# MotioGlove.net
KiCad netlist of a schematic drawn in EAGLE
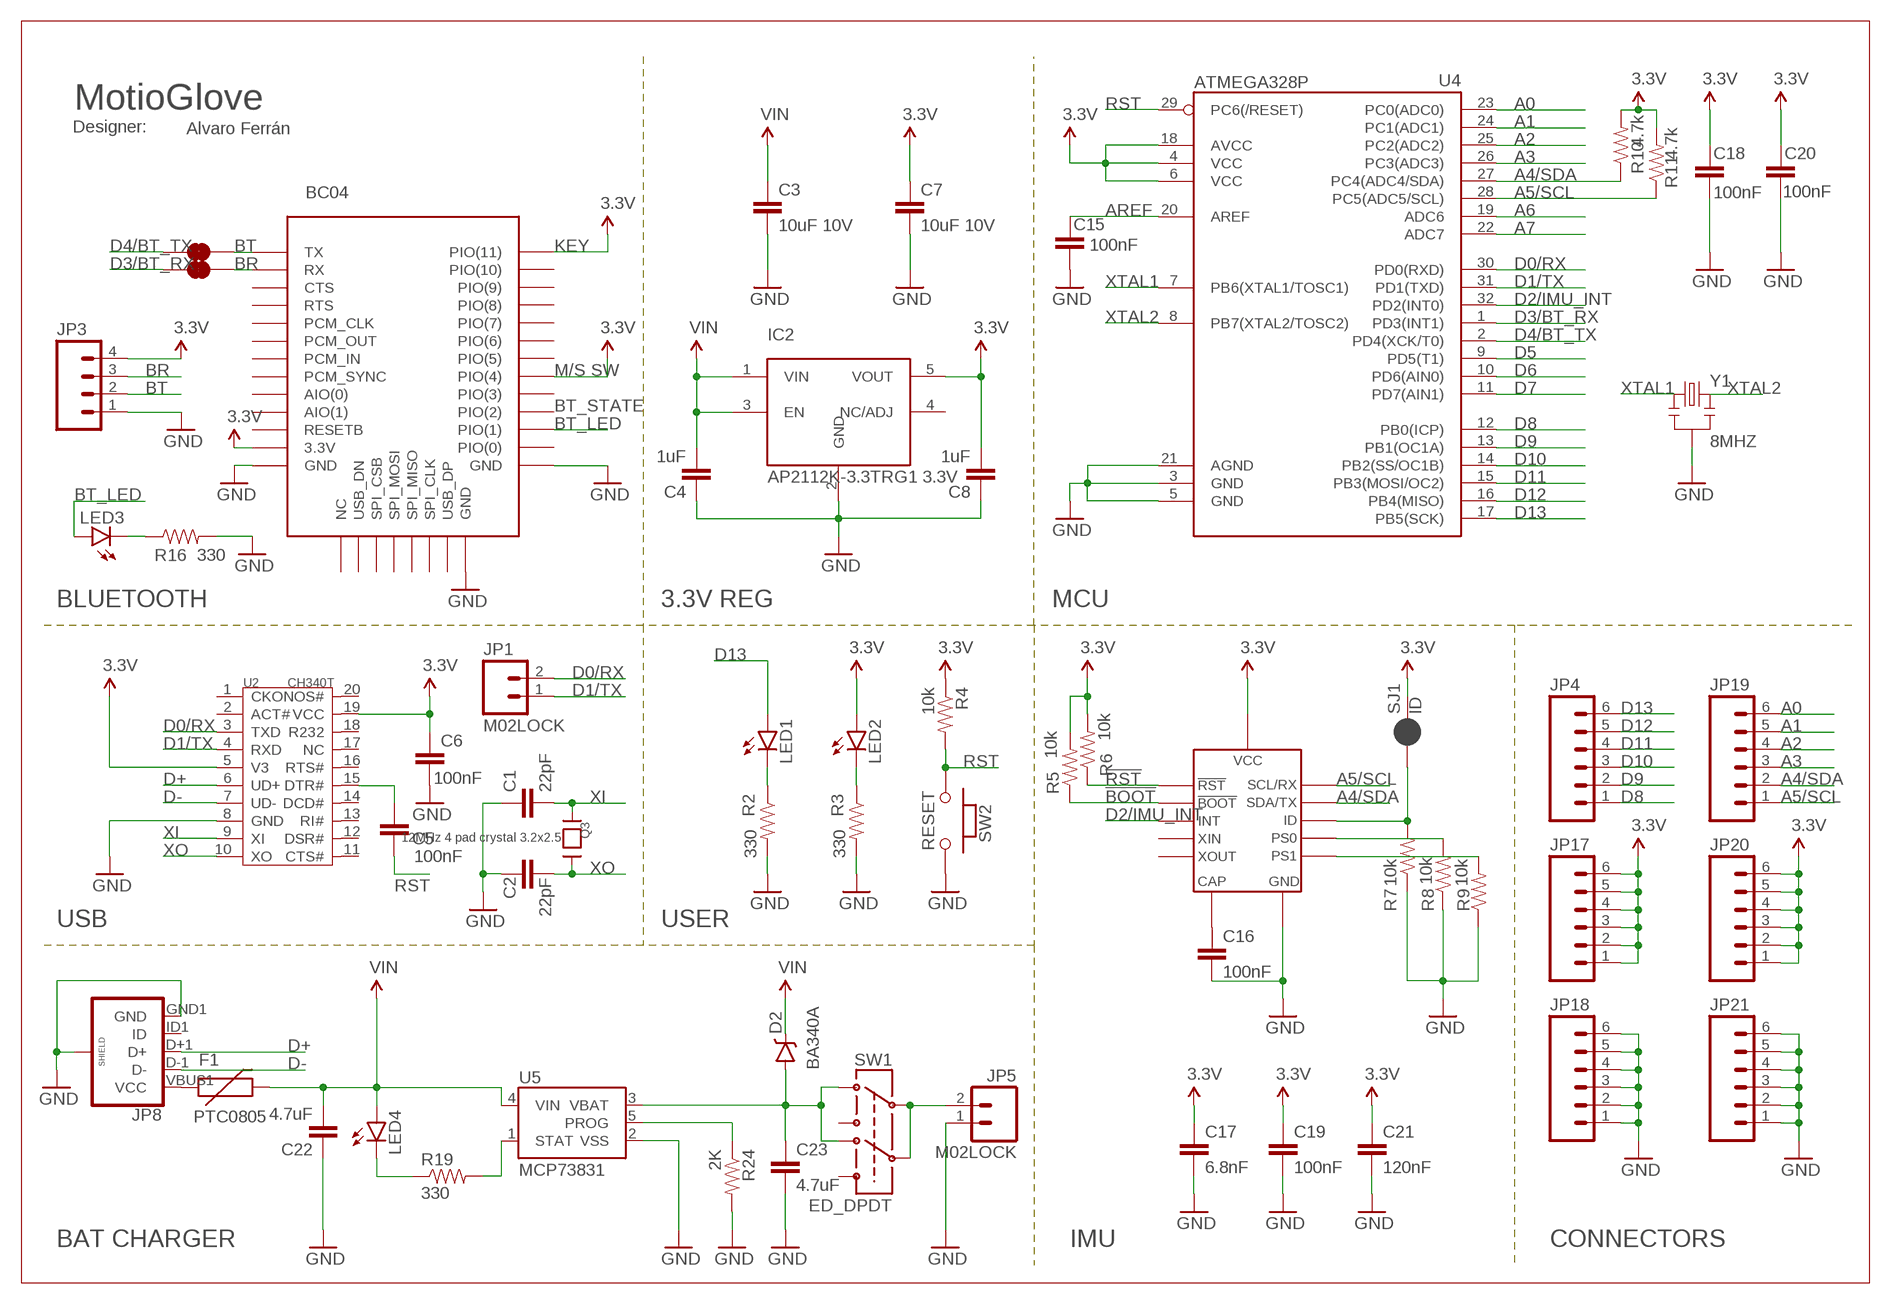
[diagram p0: schematic, sheet 1]

(export (version "E")
  (design (tool "Eeschema 10.0.6"))
  (components
    (comp (ref "C1")
      (value "22pF")
      (footprint "eagle-import:0402-CAP")
      (libsource (lib "eagle-import") (part "CAP0402-CAP"))
    )
    (comp (ref "C2")
      (value "22pF")
      (footprint "eagle-import:0402-CAP")
      (libsource (lib "eagle-import") (part "CAP0402-CAP"))
    )
    (comp (ref "C3")
      (value "10uF 10V")
      (footprint "eagle-import:0603-CAP")
      (libsource (lib "eagle-import") (part "CAP0603-CAP"))
    )
    (comp (ref "C4")
      (value "1uF")
      (footprint "eagle-import:0603-CAP")
      (libsource (lib "eagle-import") (part "CAP0603-CAP"))
    )
    (comp (ref "C5")
      (value "100nF")
      (footprint "eagle-import:0402-CAP")
      (libsource (lib "eagle-import") (part "CAP0402-CAP"))
    )
    (comp (ref "C6")
      (value "100nF")
      (footprint "eagle-import:0402-CAP")
      (libsource (lib "eagle-import") (part "CAP0402-CAP"))
    )
    (comp (ref "C7")
      (value "10uF 10V")
      (footprint "eagle-import:0603-CAP")
      (libsource (lib "eagle-import") (part "CAP0603-CAP"))
    )
    (comp (ref "C8")
      (value "1uF")
      (footprint "eagle-import:0603-CAP")
      (libsource (lib "eagle-import") (part "CAP0603-CAP"))
    )
    (comp (ref "C15")
      (value "100nF")
      (footprint "eagle-import:0402-CAP")
      (libsource (lib "eagle-import") (part "CAP0402-CAP"))
    )
    (comp (ref "C16")
      (value "100nF")
      (footprint "eagle-import:0603-CAP")
      (libsource (lib "eagle-import") (part "CAP0603-CAP"))
    )
    (comp (ref "C17")
      (value "6.8nF")
      (footprint "eagle-import:0603-CAP")
      (libsource (lib "eagle-import") (part "CAP0603-CAP"))
    )
    (comp (ref "C18")
      (value "100nF")
      (footprint "eagle-import:0402-CAP")
      (libsource (lib "eagle-import") (part "CAP0402-CAP"))
    )
    (comp (ref "C19")
      (value "100nF")
      (footprint "eagle-import:0603-CAP")
      (libsource (lib "eagle-import") (part "CAP0603-CAP"))
    )
    (comp (ref "C20")
      (value "100nF")
      (footprint "eagle-import:0402-CAP")
      (libsource (lib "eagle-import") (part "CAP0402-CAP"))
    )
    (comp (ref "C21")
      (value "120nF")
      (footprint "eagle-import:0603-CAP")
      (libsource (lib "eagle-import") (part "CAP0603-CAP"))
    )
    (comp (ref "C22")
      (value "4.7uF")
      (footprint "eagle-import:0402-CAP")
      (libsource (lib "eagle-import") (part "CAP0402-CAP"))
    )
    (comp (ref "C23")
      (value "4.7uF")
      (footprint "eagle-import:0402-CAP")
      (libsource (lib "eagle-import") (part "CAP0402-CAP"))
    )
    (comp (ref "D2")
      (value "BA340A")
      (footprint "eagle-import:SMA-DIODE")
      (libsource (lib "eagle-import") (part "B340A"))
    )
    (comp (ref "F1")
      (value "PTC0805")
      (footprint "eagle-import:0805")
      (libsource (lib "eagle-import") (part "PTC0805"))
    )
    (comp (ref "IC2")
      (value "AP2112K-3.3TRG1 3.3V")
      (footprint "eagle-import:SOT23-5")
      (libsource (lib "eagle-import") (part "5PIN_REG"))
    )
    (comp (ref "IC3")
      (value "BC04_BLUETOOTH")
      (footprint "eagle-import:BC04")
      (libsource (lib "eagle-import") (part "BC04_BLUETOOTH"))
    )
    (comp (ref "JP1")
      (value "M02LOCK")
      (footprint "eagle-import:1X02_LOCK")
      (libsource (lib "eagle-import") (part "M02LOCK"))
    )
    (comp (ref "JP3")
      (value "M04LOCK")
      (footprint "eagle-import:1X04_LOCK")
      (libsource (lib "eagle-import") (part "M04LOCK"))
    )
    (comp (ref "JP4")
      (value "M06LOCK")
      (footprint "eagle-import:1X06_LOCK")
      (libsource (lib "eagle-import") (part "M06LOCK"))
    )
    (comp (ref "JP5")
      (value "M02LOCK")
      (footprint "eagle-import:1X02_LOCK")
      (libsource (lib "eagle-import") (part "M02LOCK"))
    )
    (comp (ref "JP8")
      (value "USB_MICROB_PLUGCONN-11752")
      (footprint "eagle-import:USB-B-MICRO-SMD_V03")
      (libsource (lib "eagle-import") (part "USB_MICROB_PLUGCONN-11752"))
    )
    (comp (ref "JP17")
      (value "M06LOCK")
      (footprint "eagle-import:1X06_LOCK")
      (libsource (lib "eagle-import") (part "M06LOCK"))
    )
    (comp (ref "JP18")
      (value "M06LOCK")
      (footprint "eagle-import:1X06_LOCK")
      (libsource (lib "eagle-import") (part "M06LOCK"))
    )
    (comp (ref "JP19")
      (value "M06LOCK")
      (footprint "eagle-import:1X06_LOCK")
      (libsource (lib "eagle-import") (part "M06LOCK"))
    )
    (comp (ref "JP20")
      (value "M06LOCK")
      (footprint "eagle-import:1X06_LOCK")
      (libsource (lib "eagle-import") (part "M06LOCK"))
    )
    (comp (ref "JP21")
      (value "M06LOCK")
      (footprint "eagle-import:1X06_LOCK")
      (libsource (lib "eagle-import") (part "M06LOCK"))
    )
    (comp (ref "LED1")
      (value "LED0603")
      (footprint "eagle-import:LED-0603")
      (libsource (lib "eagle-import") (part "LED0603"))
    )
    (comp (ref "LED2")
      (value "LED0603")
      (footprint "eagle-import:LED-0603")
      (libsource (lib "eagle-import") (part "LED0603"))
    )
    (comp (ref "LED3")
      (value "LED0603")
      (footprint "eagle-import:LED-0603")
      (libsource (lib "eagle-import") (part "LED0603"))
    )
    (comp (ref "LED4")
      (value "LED0603")
      (footprint "eagle-import:LED-0603")
      (libsource (lib "eagle-import") (part "LED0603"))
    )
    (comp (ref "Q3")
      (value "12MHz 4 pad crystal 3.2x2.5")
      (footprint "eagle-import:CRYSTAL_3.2X2.5")
      (libsource (lib "eagle-import") (part "CRYSTAL3.2X2.5"))
    )
    (comp (ref "R")
      (value "JUMPER-PAD-2-NC_BY_TRACE")
      (footprint "eagle-import:PAD-JUMPER-2-NC_BY_TRACE_YES_SILK")
      (libsource (lib "eagle-import") (part "JUMPER-PAD-2-NC_BY_TRACE"))
    )
    (comp (ref "R2")
      (value "330")
      (footprint "eagle-import:0402-RES")
      (libsource (lib "eagle-import") (part "RESISTOR0402-RES"))
    )
    (comp (ref "R3")
      (value "330")
      (footprint "eagle-import:0402-RES")
      (libsource (lib "eagle-import") (part "RESISTOR0402-RES"))
    )
    (comp (ref "R4")
      (value "10k")
      (footprint "eagle-import:0402-RES")
      (libsource (lib "eagle-import") (part "RESISTOR0402-RES"))
    )
    (comp (ref "R5")
      (value "10k")
      (footprint "eagle-import:0402-RES")
      (libsource (lib "eagle-import") (part "RESISTOR0402-RES"))
    )
    (comp (ref "R6")
      (value "10k")
      (footprint "eagle-import:0402-RES")
      (libsource (lib "eagle-import") (part "RESISTOR0402-RES"))
    )
    (comp (ref "R7")
      (value "10k")
      (footprint "eagle-import:0402-RES")
      (libsource (lib "eagle-import") (part "RESISTOR0402-RES"))
    )
    (comp (ref "R8")
      (value "10k")
      (footprint "eagle-import:0402-RES")
      (libsource (lib "eagle-import") (part "RESISTOR0402-RES"))
    )
    (comp (ref "R9")
      (value "10k")
      (footprint "eagle-import:0402-RES")
      (libsource (lib "eagle-import") (part "RESISTOR0402-RES"))
    )
    (comp (ref "R10")
      (value "4.7k")
      (footprint "eagle-import:0402-RES")
      (libsource (lib "eagle-import") (part "RESISTOR0402-RES"))
    )
    (comp (ref "R11")
      (value "4.7k")
      (footprint "eagle-import:0402-RES")
      (libsource (lib "eagle-import") (part "RESISTOR0402-RES"))
    )
    (comp (ref "R16")
      (value "330")
      (footprint "eagle-import:0402-RES")
      (libsource (lib "eagle-import") (part "RESISTOR0402-RES"))
    )
    (comp (ref "R19")
      (value "330")
      (footprint "eagle-import:0402-RES")
      (libsource (lib "eagle-import") (part "RESISTOR0402-RES"))
    )
    (comp (ref "R24")
      (value "2K")
      (footprint "eagle-import:0402-RES")
      (libsource (lib "eagle-import") (part "RESISTOR0402-RES"))
    )
    (comp (ref "SJ1")
      (value "ID")
      (footprint "eagle-import:PAD-JUMPER-2-NC_BY_PASTE_YES_SILK")
      (libsource (lib "eagle-import") (part "JUMPER-PAD-2-NC_BY_PASTE"))
    )
    (comp (ref "SW1")
      (value "ED_DPDT")
      (footprint "eagle-import:ED_DPDT")
      (libsource (lib "eagle-import") (part "ED_DPDT"))
    )
    (comp (ref "SW2")
      (value "RESET")
      (footprint "eagle-import:157SW")
      (libsource (lib "eagle-import") (part "PB157"))
    )
    (comp (ref "T")
      (value "JUMPER-PAD-2-NC_BY_TRACE")
      (footprint "eagle-import:PAD-JUMPER-2-NC_BY_TRACE_YES_SILK")
      (libsource (lib "eagle-import") (part "JUMPER-PAD-2-NC_BY_TRACE"))
    )
    (comp (ref "U2")
      (value "CH340T")
      (footprint "eagle-import:SSOP20")
      (libsource (lib "eagle-import") (part "CH340T"))
    )
    (comp (ref "U3")
      (value "BNO055")
      (footprint "eagle-import:BNO055")
      (libsource (lib "eagle-import") (part "BNO055"))
    )
    (comp (ref "U4")
      (value "ATMEGA328P")
      (footprint "eagle-import:TQFP32-08")
      (libsource (lib "eagle-import") (part "ATMEGA328_SMT"))
    )
    (comp (ref "U5")
      (value "MCP73831")
      (footprint "eagle-import:SOT23-5")
      (libsource (lib "eagle-import") (part "MCP73831"))
    )
    (comp (ref "Y1")
      (value "8MHZ")
      (footprint "eagle-import:RESONATOR-SMD")
      (libsource (lib "eagle-import") (part "RESONATOR8MHZ"))
    )
  )
  (nets
    (net (code "1") (name "/A0") (class "Default")
      (node (ref "JP19") (pin "6") (pinfunction "6_6") (pintype "passive"))
      (node (ref "U4") (pin "23") (pinfunction "PC0(ADC0)_23") (pintype "bidirectional"))
    )
    (net (code "2") (name "/A1") (class "Default")
      (node (ref "JP19") (pin "5") (pinfunction "5_5") (pintype "passive"))
      (node (ref "U4") (pin "24") (pinfunction "PC1(ADC1)_24") (pintype "bidirectional"))
    )
    (net (code "3") (name "/A2") (class "Default")
      (node (ref "JP19") (pin "4") (pinfunction "4_4") (pintype "passive"))
      (node (ref "U4") (pin "25") (pinfunction "PC2(ADC2)_25") (pintype "bidirectional"))
    )
    (net (code "4") (name "/A3") (class "Default")
      (node (ref "JP19") (pin "3") (pinfunction "3_3") (pintype "passive"))
      (node (ref "U4") (pin "26") (pinfunction "PC3(ADC3)_26") (pintype "bidirectional"))
    )
    (net (code "5") (name "/A4{slash}SDA") (class "Default")
      (node (ref "JP19") (pin "2") (pinfunction "2_2") (pintype "passive"))
      (node (ref "R10") (pin "1") (pinfunction "1_1") (pintype "passive"))
      (node (ref "U3") (pin "20") (pinfunction "SDA/TX_20") (pintype "bidirectional"))
      (node (ref "U4") (pin "27") (pinfunction "PC4(ADC4/SDA)_27") (pintype "bidirectional"))
    )
    (net (code "6") (name "/A5{slash}SCL") (class "Default")
      (node (ref "JP19") (pin "1") (pinfunction "1_1") (pintype "passive"))
      (node (ref "R11") (pin "1") (pinfunction "1_1") (pintype "passive"))
      (node (ref "U3") (pin "19") (pinfunction "SCL/RX_19") (pintype "bidirectional"))
      (node (ref "U4") (pin "28") (pinfunction "PC5(ADC5/SCL)_28") (pintype "bidirectional"))
    )
    (net (code "7") (name "/A6") (class "Default")
      (node (ref "U4") (pin "19") (pinfunction "ADC6_19") (pintype "bidirectional"))
    )
    (net (code "8") (name "/A7") (class "Default")
      (node (ref "U4") (pin "22") (pinfunction "ADC7_22") (pintype "bidirectional"))
    )
    (net (code "9") (name "/AREF") (class "Default")
      (node (ref "C15") (pin "1") (pinfunction "1_1") (pintype "passive"))
      (node (ref "U4") (pin "20") (pinfunction "AREF_20") (pintype "bidirectional"))
    )
    (net (code "10") (name "/BR") (class "Default")
      (node (ref "IC3") (pin "P$2") (pinfunction "RX_P$2") (pintype "bidirectional"))
      (node (ref "JP3") (pin "3") (pinfunction "3_3") (pintype "passive"))
      (node (ref "R") (pin "2") (pinfunction "2_2") (pintype "passive"))
    )
    (net (code "11") (name "/BT") (class "Default")
      (node (ref "IC3") (pin "P$1") (pinfunction "TX_P$1") (pintype "bidirectional"))
      (node (ref "JP3") (pin "2") (pinfunction "2_2") (pintype "passive"))
      (node (ref "T") (pin "2") (pinfunction "2_2") (pintype "passive"))
    )
    (net (code "12") (name "/BT_LED") (class "Default")
      (node (ref "IC3") (pin "P$24") (pinfunction "PIO(1)_P$24") (pintype "bidirectional"))
      (node (ref "LED3") (pin "A") (pinfunction "A_A") (pintype "passive"))
    )
    (net (code "13") (name "/D+") (class "Default")
      (node (ref "JP8") (pin "D+1") (pinfunction "D+_D+1") (pintype "bidirectional"))
      (node (ref "U2") (pin "6") (pinfunction "UD+_6") (pintype "bidirectional"))
    )
    (net (code "14") (name "/D-") (class "Default")
      (node (ref "JP8") (pin "D-1") (pinfunction "D-_D-1") (pintype "bidirectional"))
      (node (ref "U2") (pin "7") (pinfunction "UD-_7") (pintype "bidirectional"))
    )
    (net (code "15") (name "/D0{slash}RX") (class "Default")
      (node (ref "JP1") (pin "2") (pinfunction "2_2") (pintype "passive"))
      (node (ref "U2") (pin "3") (pinfunction "TXD_3") (pintype "output"))
      (node (ref "U4") (pin "30") (pinfunction "PD0(RXD)_30") (pintype "bidirectional"))
    )
    (net (code "16") (name "/D1{slash}TX") (class "Default")
      (node (ref "JP1") (pin "1") (pinfunction "1_1") (pintype "passive"))
      (node (ref "U2") (pin "4") (pinfunction "RXD_4") (pintype "input"))
      (node (ref "U4") (pin "31") (pinfunction "PD1(TXD)_31") (pintype "bidirectional"))
    )
    (net (code "17") (name "/D2{slash}IMU_INT") (class "Default")
      (node (ref "U3") (pin "14") (pinfunction "INT_14") (pintype "bidirectional"))
      (node (ref "U4") (pin "32") (pinfunction "PD2(INT0)_32") (pintype "bidirectional"))
    )
    (net (code "18") (name "/D3{slash}BT_RX") (class "Default")
      (node (ref "R") (pin "1") (pinfunction "1_1") (pintype "passive"))
      (node (ref "U4") (pin "1") (pinfunction "PD3(INT1)_1") (pintype "bidirectional"))
    )
    (net (code "19") (name "/D4{slash}BT_TX") (class "Default")
      (node (ref "T") (pin "1") (pinfunction "1_1") (pintype "passive"))
      (node (ref "U4") (pin "2") (pinfunction "PD4(XCK/T0)_2") (pintype "bidirectional"))
    )
    (net (code "20") (name "/D5") (class "Default")
      (node (ref "U4") (pin "9") (pinfunction "PD5(T1)_9") (pintype "bidirectional"))
    )
    (net (code "21") (name "/D6") (class "Default")
      (node (ref "U4") (pin "10") (pinfunction "PD6(AIN0)_10") (pintype "bidirectional"))
    )
    (net (code "22") (name "/D7") (class "Default")
      (node (ref "U4") (pin "11") (pinfunction "PD7(AIN1)_11") (pintype "bidirectional"))
    )
    (net (code "23") (name "/D8") (class "Default")
      (node (ref "JP4") (pin "1") (pinfunction "1_1") (pintype "passive"))
      (node (ref "U4") (pin "12") (pinfunction "PB0(ICP)_12") (pintype "bidirectional"))
    )
    (net (code "24") (name "/D9") (class "Default")
      (node (ref "JP4") (pin "2") (pinfunction "2_2") (pintype "passive"))
      (node (ref "U4") (pin "13") (pinfunction "PB1(OC1A)_13") (pintype "bidirectional"))
    )
    (net (code "25") (name "/D10") (class "Default")
      (node (ref "JP4") (pin "3") (pinfunction "3_3") (pintype "passive"))
      (node (ref "U4") (pin "14") (pinfunction "PB2(SS/OC1B)_14") (pintype "bidirectional"))
    )
    (net (code "26") (name "/D11") (class "Default")
      (node (ref "JP4") (pin "4") (pinfunction "4_4") (pintype "passive"))
      (node (ref "U4") (pin "15") (pinfunction "PB3(MOSI/OC2)_15") (pintype "bidirectional"))
    )
    (net (code "27") (name "/D12") (class "Default")
      (node (ref "JP4") (pin "5") (pinfunction "5_5") (pintype "passive"))
      (node (ref "U4") (pin "16") (pinfunction "PB4(MISO)_16") (pintype "bidirectional"))
    )
    (net (code "28") (name "/D13") (class "Default")
      (node (ref "JP4") (pin "6") (pinfunction "6_6") (pintype "passive"))
      (node (ref "LED1") (pin "A") (pinfunction "A_A") (pintype "passive"))
      (node (ref "U4") (pin "17") (pinfunction "PB5(SCK)_17") (pintype "bidirectional"))
    )
    (net (code "29") (name "/NOS#") (class "Default")
      (node (ref "U2") (pin "20") (pinfunction "NOS#_20") (pintype "power_in"))
    )
    (net (code "30") (name "/RST") (class "Default")
      (node (ref "C5") (pin "2") (pinfunction "2_2") (pintype "passive"))
      (node (ref "R4") (pin "2") (pinfunction "2_2") (pintype "passive"))
      (node (ref "SW2") (pin "1") (pinfunction "1_1") (pintype "passive"))
      (node (ref "U4") (pin "29") (pinfunction "PC6(/RESET)_29") (pintype "bidirectional"))
    )
    (net (code "31") (name "/XI") (class "Default")
      (node (ref "C1") (pin "2") (pinfunction "2_2") (pintype "passive"))
      (node (ref "Q3") (pin "3") (pinfunction "P$2_3") (pintype "passive"))
      (node (ref "U2") (pin "9") (pinfunction "XI_9") (pintype "input"))
    )
    (net (code "32") (name "/XO") (class "Default")
      (node (ref "C2") (pin "2") (pinfunction "2_2") (pintype "passive"))
      (node (ref "Q3") (pin "1") (pinfunction "P$1_1") (pintype "passive"))
      (node (ref "U2") (pin "10") (pinfunction "XO_10") (pintype "output"))
    )
    (net (code "33") (name "/XTAL1") (class "Default")
      (node (ref "U4") (pin "7") (pinfunction "PB6(XTAL1/TOSC1)_7") (pintype "bidirectional"))
      (node (ref "Y1") (pin "1") (pinfunction "1_1") (pintype "passive"))
    )
    (net (code "34") (name "/XTAL2") (class "Default")
      (node (ref "U4") (pin "8") (pinfunction "PB7(XTAL2/TOSC2)_8") (pintype "bidirectional"))
      (node (ref "Y1") (pin "3") (pinfunction "3_3") (pintype "passive"))
    )
    (net (code "35") (name "/~{BOOT}") (class "Default")
      (node (ref "R5") (pin "1") (pinfunction "1_1") (pintype "passive"))
      (node (ref "U3") (pin "4") (pinfunction "BOOT_4") (pintype "bidirectional"))
    )
    (net (code "36") (name "/~{RST}") (class "Default")
      (node (ref "R6") (pin "1") (pinfunction "1_1") (pintype "passive"))
      (node (ref "U3") (pin "11") (pinfunction "RST_11") (pintype "bidirectional"))
    )
    (net (code "37") (name "3.3V") (class "Default")
      (node (ref "C17") (pin "1") (pinfunction "1_1") (pintype "passive"))
      (node (ref "C18") (pin "1") (pinfunction "1_1") (pintype "passive"))
      (node (ref "C19") (pin "1") (pinfunction "1_1") (pintype "passive"))
      (node (ref "C20") (pin "1") (pinfunction "1_1") (pintype "passive"))
      (node (ref "C21") (pin "1") (pinfunction "1_1") (pintype "passive"))
      (node (ref "C6") (pin "1") (pinfunction "1_1") (pintype "passive"))
      (node (ref "C7") (pin "1") (pinfunction "1_1") (pintype "passive"))
      (node (ref "C8") (pin "2") (pinfunction "2_2") (pintype "passive"))
      (node (ref "IC2") (pin "5") (pinfunction "VOUT_5") (pintype "bidirectional"))
      (node (ref "IC3") (pin "P$12") (pinfunction "3.3V_P$12") (pintype "bidirectional"))
      (node (ref "IC3") (pin "P$27") (pinfunction "PIO(4)_P$27") (pintype "bidirectional"))
      (node (ref "IC3") (pin "P$34") (pinfunction "PIO(11)_P$34") (pintype "bidirectional"))
      (node (ref "JP17") (pin "1") (pinfunction "1_1") (pintype "passive"))
      (node (ref "JP17") (pin "2") (pinfunction "2_2") (pintype "passive"))
      (node (ref "JP17") (pin "3") (pinfunction "3_3") (pintype "passive"))
      (node (ref "JP17") (pin "4") (pinfunction "4_4") (pintype "passive"))
      (node (ref "JP17") (pin "5") (pinfunction "5_5") (pintype "passive"))
      (node (ref "JP17") (pin "6") (pinfunction "6_6") (pintype "passive"))
      (node (ref "JP20") (pin "1") (pinfunction "1_1") (pintype "passive"))
      (node (ref "JP20") (pin "2") (pinfunction "2_2") (pintype "passive"))
      (node (ref "JP20") (pin "3") (pinfunction "3_3") (pintype "passive"))
      (node (ref "JP20") (pin "4") (pinfunction "4_4") (pintype "passive"))
      (node (ref "JP20") (pin "5") (pinfunction "5_5") (pintype "passive"))
      (node (ref "JP20") (pin "6") (pinfunction "6_6") (pintype "passive"))
      (node (ref "JP3") (pin "4") (pinfunction "4_4") (pintype "passive"))
      (node (ref "LED2") (pin "A") (pinfunction "A_A") (pintype "passive"))
      (node (ref "R10") (pin "2") (pinfunction "2_2") (pintype "passive"))
      (node (ref "R11") (pin "2") (pinfunction "2_2") (pintype "passive"))
      (node (ref "R4") (pin "1") (pinfunction "1_1") (pintype "passive"))
      (node (ref "R5") (pin "2") (pinfunction "2_2") (pintype "passive"))
      (node (ref "R6") (pin "2") (pinfunction "2_2") (pintype "passive"))
      (node (ref "SJ1") (pin "2") (pinfunction "2_2") (pintype "passive"))
      (node (ref "U2") (pin "19") (pinfunction "VCC_19") (pintype "power_in"))
      (node (ref "U2") (pin "5") (pinfunction "V3_5") (pintype "power_in"))
      (node (ref "U3") (pin "28") (pinfunction "VCC_28") (pintype "bidirectional"))
      (node (ref "U3") (pin "3") (pinfunction "VCC_3") (pintype "bidirectional"))
      (node (ref "U4") (pin "18") (pinfunction "AVCC_18") (pintype "bidirectional"))
      (node (ref "U4") (pin "4") (pinfunction "VCC_4") (pintype "bidirectional"))
      (node (ref "U4") (pin "6") (pinfunction "VCC_6") (pintype "bidirectional"))
    )
    (net (code "38") (name "GND") (class "Default")
      (node (ref "C1") (pin "1") (pinfunction "1_1") (pintype "passive"))
      (node (ref "C15") (pin "2") (pinfunction "2_2") (pintype "passive"))
      (node (ref "C16") (pin "2") (pinfunction "2_2") (pintype "passive"))
      (node (ref "C17") (pin "2") (pinfunction "2_2") (pintype "passive"))
      (node (ref "C18") (pin "2") (pinfunction "2_2") (pintype "passive"))
      (node (ref "C19") (pin "2") (pinfunction "2_2") (pintype "passive"))
      (node (ref "C2") (pin "1") (pinfunction "1_1") (pintype "passive"))
      (node (ref "C20") (pin "2") (pinfunction "2_2") (pintype "passive"))
      (node (ref "C21") (pin "2") (pinfunction "2_2") (pintype "passive"))
      (node (ref "C22") (pin "1") (pinfunction "1_1") (pintype "passive"))
      (node (ref "C23") (pin "2") (pinfunction "2_2") (pintype "passive"))
      (node (ref "C3") (pin "2") (pinfunction "2_2") (pintype "passive"))
      (node (ref "C4") (pin "1") (pinfunction "1_1") (pintype "passive"))
      (node (ref "C6") (pin "2") (pinfunction "2_2") (pintype "passive"))
      (node (ref "C7") (pin "2") (pinfunction "2_2") (pintype "passive"))
      (node (ref "C8") (pin "1") (pinfunction "1_1") (pintype "passive"))
      (node (ref "IC2") (pin "2") (pinfunction "GND_2") (pintype "bidirectional"))
      (node (ref "IC3") (pin "P$13") (pinfunction "GND_P$13") (pintype "bidirectional"))
      (node (ref "IC3") (pin "P$21") (pinfunction "GND_P$21") (pintype "bidirectional"))
      (node (ref "IC3") (pin "P$22") (pinfunction "GND_P$22") (pintype "bidirectional"))
      (node (ref "JP18") (pin "1") (pinfunction "1_1") (pintype "passive"))
      (node (ref "JP18") (pin "2") (pinfunction "2_2") (pintype "passive"))
      (node (ref "JP18") (pin "3") (pinfunction "3_3") (pintype "passive"))
      (node (ref "JP18") (pin "4") (pinfunction "4_4") (pintype "passive"))
      (node (ref "JP18") (pin "5") (pinfunction "5_5") (pintype "passive"))
      (node (ref "JP18") (pin "6") (pinfunction "6_6") (pintype "passive"))
      (node (ref "JP21") (pin "1") (pinfunction "1_1") (pintype "passive"))
      (node (ref "JP21") (pin "2") (pinfunction "2_2") (pintype "passive"))
      (node (ref "JP21") (pin "3") (pinfunction "3_3") (pintype "passive"))
      (node (ref "JP21") (pin "4") (pinfunction "4_4") (pintype "passive"))
      (node (ref "JP21") (pin "5") (pinfunction "5_5") (pintype "passive"))
      (node (ref "JP21") (pin "6") (pinfunction "6_6") (pintype "passive"))
      (node (ref "JP3") (pin "1") (pinfunction "1_1") (pintype "passive"))
      (node (ref "JP5") (pin "1") (pinfunction "1_1") (pintype "passive"))
      (node (ref "JP8") (pin "GND1") (pinfunction "GND_GND1") (pintype "bidirectional"))
      (node (ref "JP8") (pin "SHIELD1") (pinfunction "SHIELD_SHIELD1") (pintype "bidirectional"))
      (node (ref "JP8") (pin "SHIELD2") (pinfunction "SHIELD_SHIELD2") (pintype "bidirectional"))
      (node (ref "JP8") (pin "SHIELD3") (pinfunction "SHIELD_SHIELD3") (pintype "bidirectional"))
      (node (ref "R16") (pin "2") (pinfunction "2_2") (pintype "passive"))
      (node (ref "R2") (pin "2") (pinfunction "2_2") (pintype "passive"))
      (node (ref "R24") (pin "2") (pinfunction "2_2") (pintype "passive"))
      (node (ref "R3") (pin "2") (pinfunction "2_2") (pintype "passive"))
      (node (ref "R7") (pin "1") (pinfunction "1_1") (pintype "passive"))
      (node (ref "R8") (pin "1") (pinfunction "1_1") (pintype "passive"))
      (node (ref "R9") (pin "1") (pinfunction "1_1") (pintype "passive"))
      (node (ref "SW2") (pin "2") (pinfunction "2_2") (pintype "passive"))
      (node (ref "U2") (pin "8") (pinfunction "GND_8") (pintype "power_in"))
      (node (ref "U3") (pin "10") (pinfunction "GND_10") (pintype "power_in"))
      (node (ref "U3") (pin "15") (pinfunction "GND_15") (pintype "power_in"))
      (node (ref "U3") (pin "16") (pinfunction "GND_16") (pintype "power_in"))
      (node (ref "U3") (pin "18") (pinfunction "GND_18") (pintype "power_in"))
      (node (ref "U3") (pin "2") (pinfunction "GND_2") (pintype "power_in"))
      (node (ref "U3") (pin "25") (pinfunction "GND_25") (pintype "power_in"))
      (node (ref "U4") (pin "21") (pinfunction "AGND_21") (pintype "bidirectional"))
      (node (ref "U4") (pin "3") (pinfunction "GND_3") (pintype "bidirectional"))
      (node (ref "U4") (pin "5") (pinfunction "GND_5") (pintype "bidirectional"))
      (node (ref "U5") (pin "2") (pinfunction "VSS_2") (pintype "power_in"))
      (node (ref "Y1") (pin "2") (pinfunction "2_2") (pintype "passive"))
    )
    (net (code "39") (name "Net-(JP5-Pad2)") (class "Default")
      (node (ref "JP5") (pin "2") (pinfunction "2_2") (pintype "passive"))
      (node (ref "SW1") (pin "2") (pinfunction "2_2") (pintype "bidirectional"))
      (node (ref "SW1") (pin "5") (pinfunction "5_5") (pintype "bidirectional"))
    )
    (net (code "40") (name "Net-(JP8-VCC)") (class "Default")
      (node (ref "F1") (pin "1") (pinfunction "1_1") (pintype "bidirectional"))
      (node (ref "JP8") (pin "VBUS1") (pinfunction "VCC_VBUS1") (pintype "bidirectional"))
    )
    (net (code "41") (name "Net-(LED1-PadC)") (class "Default")
      (node (ref "LED1") (pin "C") (pinfunction "C_C") (pintype "passive"))
      (node (ref "R2") (pin "1") (pinfunction "1_1") (pintype "passive"))
    )
    (net (code "42") (name "Net-(LED2-PadC)") (class "Default")
      (node (ref "LED2") (pin "C") (pinfunction "C_C") (pintype "passive"))
      (node (ref "R3") (pin "1") (pinfunction "1_1") (pintype "passive"))
    )
    (net (code "43") (name "Net-(LED3-PadC)") (class "Default")
      (node (ref "LED3") (pin "C") (pinfunction "C_C") (pintype "passive"))
      (node (ref "R16") (pin "1") (pinfunction "1_1") (pintype "passive"))
    )
    (net (code "44") (name "Net-(LED4-PadC)") (class "Default")
      (node (ref "LED4") (pin "C") (pinfunction "C_C") (pintype "passive"))
      (node (ref "R19") (pin "1") (pinfunction "1_1") (pintype "passive"))
    )
    (net (code "45") (name "Net-(U2-DTR#)") (class "Default")
      (node (ref "C5") (pin "1") (pinfunction "1_1") (pintype "passive"))
      (node (ref "U2") (pin "15") (pinfunction "DTR#_15") (pintype "output"))
    )
    (net (code "46") (name "Net-(U3-CAP)") (class "Default")
      (node (ref "C16") (pin "1") (pinfunction "1_1") (pintype "passive"))
      (node (ref "U3") (pin "9") (pinfunction "CAP_9") (pintype "bidirectional"))
    )
    (net (code "47") (name "Net-(U3-ID)") (class "Default")
      (node (ref "R7") (pin "2") (pinfunction "2_2") (pintype "passive"))
      (node (ref "SJ1") (pin "1") (pinfunction "1_1") (pintype "passive"))
      (node (ref "U3") (pin "17") (pinfunction "ID_17") (pintype "bidirectional"))
    )
    (net (code "48") (name "Net-(U3-PS0)") (class "Default")
      (node (ref "R8") (pin "2") (pinfunction "2_2") (pintype "passive"))
      (node (ref "U3") (pin "6") (pinfunction "PS0_6") (pintype "bidirectional"))
    )
    (net (code "49") (name "Net-(U3-PS1)") (class "Default")
      (node (ref "R9") (pin "2") (pinfunction "2_2") (pintype "passive"))
      (node (ref "U3") (pin "5") (pinfunction "PS1_5") (pintype "bidirectional"))
    )
    (net (code "50") (name "Net-(U5-PROG)") (class "Default")
      (node (ref "R24") (pin "1") (pinfunction "1_1") (pintype "passive"))
      (node (ref "U5") (pin "5") (pinfunction "PROG_5") (pintype "input"))
    )
    (net (code "51") (name "Net-(U5-STAT)") (class "Default")
      (node (ref "R19") (pin "2") (pinfunction "2_2") (pintype "passive"))
      (node (ref "U5") (pin "1") (pinfunction "STAT_1") (pintype "output"))
    )
    (net (code "52") (name "Net-(U5-VBAT)") (class "Default")
      (node (ref "C23") (pin "1") (pinfunction "1_1") (pintype "passive"))
      (node (ref "D2") (pin "A") (pinfunction "A_A") (pintype "passive"))
      (node (ref "SW1") (pin "1") (pinfunction "1_1") (pintype "bidirectional"))
      (node (ref "SW1") (pin "4") (pinfunction "4_4") (pintype "bidirectional"))
      (node (ref "U5") (pin "3") (pinfunction "VBAT_3") (pintype "power_in"))
    )
    (net (code "53") (name "VIN") (class "Default")
      (node (ref "C22") (pin "2") (pinfunction "2_2") (pintype "passive"))
      (node (ref "C3") (pin "1") (pinfunction "1_1") (pintype "passive"))
      (node (ref "C4") (pin "2") (pinfunction "2_2") (pintype "passive"))
      (node (ref "D2") (pin "C") (pinfunction "C_C") (pintype "passive"))
      (node (ref "F1") (pin "2") (pinfunction "2_2") (pintype "bidirectional"))
      (node (ref "IC2") (pin "1") (pinfunction "VIN_1") (pintype "bidirectional"))
      (node (ref "IC2") (pin "3") (pinfunction "EN_3") (pintype "bidirectional"))
      (node (ref "LED4") (pin "A") (pinfunction "A_A") (pintype "passive"))
      (node (ref "U5") (pin "4") (pinfunction "VIN_4") (pintype "power_in"))
    )
    (net (code "54") (name "unconnected-(IC2-NC{slash}ADJ-Pad4)") (class "Default")
      (node (ref "IC2") (pin "4") (pinfunction "NC/ADJ_4") (pintype "bidirectional"))
    )
    (net (code "55") (name "unconnected-(IC3-AIO(0)-PadP$9)") (class "Default")
      (node (ref "IC3") (pin "P$9") (pinfunction "AIO(0)_P$9") (pintype "bidirectional"))
    )
    (net (code "56") (name "unconnected-(IC3-AIO(1)-PadP$10)") (class "Default")
      (node (ref "IC3") (pin "P$10") (pinfunction "AIO(1)_P$10") (pintype "bidirectional"))
    )
    (net (code "57") (name "unconnected-(IC3-CTS-PadP$3)") (class "Default")
      (node (ref "IC3") (pin "P$3") (pinfunction "CTS_P$3") (pintype "bidirectional"))
    )
    (net (code "58") (name "unconnected-(IC3-NC-PadP$14)") (class "Default")
      (node (ref "IC3") (pin "P$14") (pinfunction "NC_P$14") (pintype "bidirectional"))
    )
    (net (code "59") (name "unconnected-(IC3-PCM_CLK-PadP$5)") (class "Default")
      (node (ref "IC3") (pin "P$5") (pinfunction "PCM_CLK_P$5") (pintype "bidirectional"))
    )
    (net (code "60") (name "unconnected-(IC3-PCM_IN-PadP$7)") (class "Default")
      (node (ref "IC3") (pin "P$7") (pinfunction "PCM_IN_P$7") (pintype "bidirectional"))
    )
    (net (code "61") (name "unconnected-(IC3-PCM_OUT-PadP$6)") (class "Default")
      (node (ref "IC3") (pin "P$6") (pinfunction "PCM_OUT_P$6") (pintype "bidirectional"))
    )
    (net (code "62") (name "unconnected-(IC3-PCM_SYNC-PadP$8)") (class "Default")
      (node (ref "IC3") (pin "P$8") (pinfunction "PCM_SYNC_P$8") (pintype "bidirectional"))
    )
    (net (code "63") (name "unconnected-(IC3-PIO(0)-PadP$23)") (class "Default")
      (node (ref "IC3") (pin "P$23") (pinfunction "PIO(0)_P$23") (pintype "bidirectional"))
    )
    (net (code "64") (name "unconnected-(IC3-PIO(2)-PadP$25)") (class "Default")
      (node (ref "IC3") (pin "P$25") (pinfunction "PIO(2)_P$25") (pintype "bidirectional"))
    )
    (net (code "65") (name "unconnected-(IC3-PIO(3)-PadP$26)") (class "Default")
      (node (ref "IC3") (pin "P$26") (pinfunction "PIO(3)_P$26") (pintype "bidirectional"))
    )
    (net (code "66") (name "unconnected-(IC3-PIO(5)-PadP$28)") (class "Default")
      (node (ref "IC3") (pin "P$28") (pinfunction "PIO(5)_P$28") (pintype "bidirectional"))
    )
    (net (code "67") (name "unconnected-(IC3-PIO(6)-PadP$29)") (class "Default")
      (node (ref "IC3") (pin "P$29") (pinfunction "PIO(6)_P$29") (pintype "bidirectional"))
    )
    (net (code "68") (name "unconnected-(IC3-PIO(7)-PadP$30)") (class "Default")
      (node (ref "IC3") (pin "P$30") (pinfunction "PIO(7)_P$30") (pintype "bidirectional"))
    )
    (net (code "69") (name "unconnected-(IC3-PIO(8)-PadP$31)") (class "Default")
      (node (ref "IC3") (pin "P$31") (pinfunction "PIO(8)_P$31") (pintype "bidirectional"))
    )
    (net (code "70") (name "unconnected-(IC3-PIO(9)-PadP$32)") (class "Default")
      (node (ref "IC3") (pin "P$32") (pinfunction "PIO(9)_P$32") (pintype "bidirectional"))
    )
    (net (code "71") (name "unconnected-(IC3-PIO(10)-PadP$33)") (class "Default")
      (node (ref "IC3") (pin "P$33") (pinfunction "PIO(10)_P$33") (pintype "bidirectional"))
    )
    (net (code "72") (name "unconnected-(IC3-RESETB-PadP$11)") (class "Default")
      (node (ref "IC3") (pin "P$11") (pinfunction "RESETB_P$11") (pintype "bidirectional"))
    )
    (net (code "73") (name "unconnected-(IC3-RTS-PadP$4)") (class "Default")
      (node (ref "IC3") (pin "P$4") (pinfunction "RTS_P$4") (pintype "bidirectional"))
    )
    (net (code "74") (name "unconnected-(IC3-SPI_CLK-PadP$19)") (class "Default")
      (node (ref "IC3") (pin "P$19") (pinfunction "SPI_CLK_P$19") (pintype "bidirectional"))
    )
    (net (code "75") (name "unconnected-(IC3-SPI_CSB-PadP$16)") (class "Default")
      (node (ref "IC3") (pin "P$16") (pinfunction "SPI_CSB_P$16") (pintype "bidirectional"))
    )
    (net (code "76") (name "unconnected-(IC3-SPI_MISO-PadP$18)") (class "Default")
      (node (ref "IC3") (pin "P$18") (pinfunction "SPI_MISO_P$18") (pintype "bidirectional"))
    )
    (net (code "77") (name "unconnected-(IC3-SPI_MOSI-PadP$17)") (class "Default")
      (node (ref "IC3") (pin "P$17") (pinfunction "SPI_MOSI_P$17") (pintype "bidirectional"))
    )
    (net (code "78") (name "unconnected-(IC3-USB_DN-PadP$15)") (class "Default")
      (node (ref "IC3") (pin "P$15") (pinfunction "USB_DN_P$15") (pintype "bidirectional"))
    )
    (net (code "79") (name "unconnected-(IC3-USB_DP-PadP$20)") (class "Default")
      (node (ref "IC3") (pin "P$20") (pinfunction "USB_DP_P$20") (pintype "bidirectional"))
    )
    (net (code "80") (name "unconnected-(JP8-ID-PadID1)") (class "Default")
      (node (ref "JP8") (pin "ID1") (pinfunction "ID_ID1") (pintype "bidirectional"))
    )
    (net (code "81") (name "unconnected-(SW1-Pad3)") (class "Default")
      (node (ref "SW1") (pin "3") (pinfunction "3_3") (pintype "bidirectional"))
    )
    (net (code "82") (name "unconnected-(SW1-Pad6)") (class "Default")
      (node (ref "SW1") (pin "6") (pinfunction "6_6") (pintype "bidirectional"))
    )
    (net (code "83") (name "unconnected-(U2-ACT#-Pad2)") (class "Default")
      (node (ref "U2") (pin "2") (pinfunction "ACT#_2") (pintype "output"))
    )
    (net (code "84") (name "unconnected-(U2-CKO-Pad1)") (class "Default")
      (node (ref "U2") (pin "1") (pinfunction "CKO_1") (pintype "output"))
    )
    (net (code "85") (name "unconnected-(U2-CTS#-Pad11)") (class "Default")
      (node (ref "U2") (pin "11") (pinfunction "CTS#_11") (pintype "input"))
    )
    (net (code "86") (name "unconnected-(U2-DCD#-Pad14)") (class "Default")
      (node (ref "U2") (pin "14") (pinfunction "DCD#_14") (pintype "input"))
    )
    (net (code "87") (name "unconnected-(U2-DSR#-Pad12)") (class "Default")
      (node (ref "U2") (pin "12") (pinfunction "DSR#_12") (pintype "input"))
    )
    (net (code "88") (name "unconnected-(U2-NC-Pad17)") (class "Default")
      (node (ref "U2") (pin "17") (pinfunction "NC_17") (pintype "no_connect"))
    )
    (net (code "89") (name "unconnected-(U2-R232-Pad18)") (class "Default")
      (node (ref "U2") (pin "18") (pinfunction "R232_18") (pintype "input"))
    )
    (net (code "90") (name "unconnected-(U2-RI#-Pad13)") (class "Default")
      (node (ref "U2") (pin "13") (pinfunction "RI#_13") (pintype "input"))
    )
    (net (code "91") (name "unconnected-(U2-RTS#-Pad16)") (class "Default")
      (node (ref "U2") (pin "16") (pinfunction "RTS#_16") (pintype "output"))
    )
    (net (code "92") (name "unconnected-(U3-XIN-Pad27)") (class "Default")
      (node (ref "U3") (pin "27") (pinfunction "XIN_27") (pintype "bidirectional"))
    )
    (net (code "93") (name "unconnected-(U3-XOUT-Pad26)") (class "Default")
      (node (ref "U3") (pin "26") (pinfunction "XOUT_26") (pintype "bidirectional"))
    )
  )
)
